# blackfin_c_ethernet.net
KiCad netlist of a schematic drawn in Altium Designer
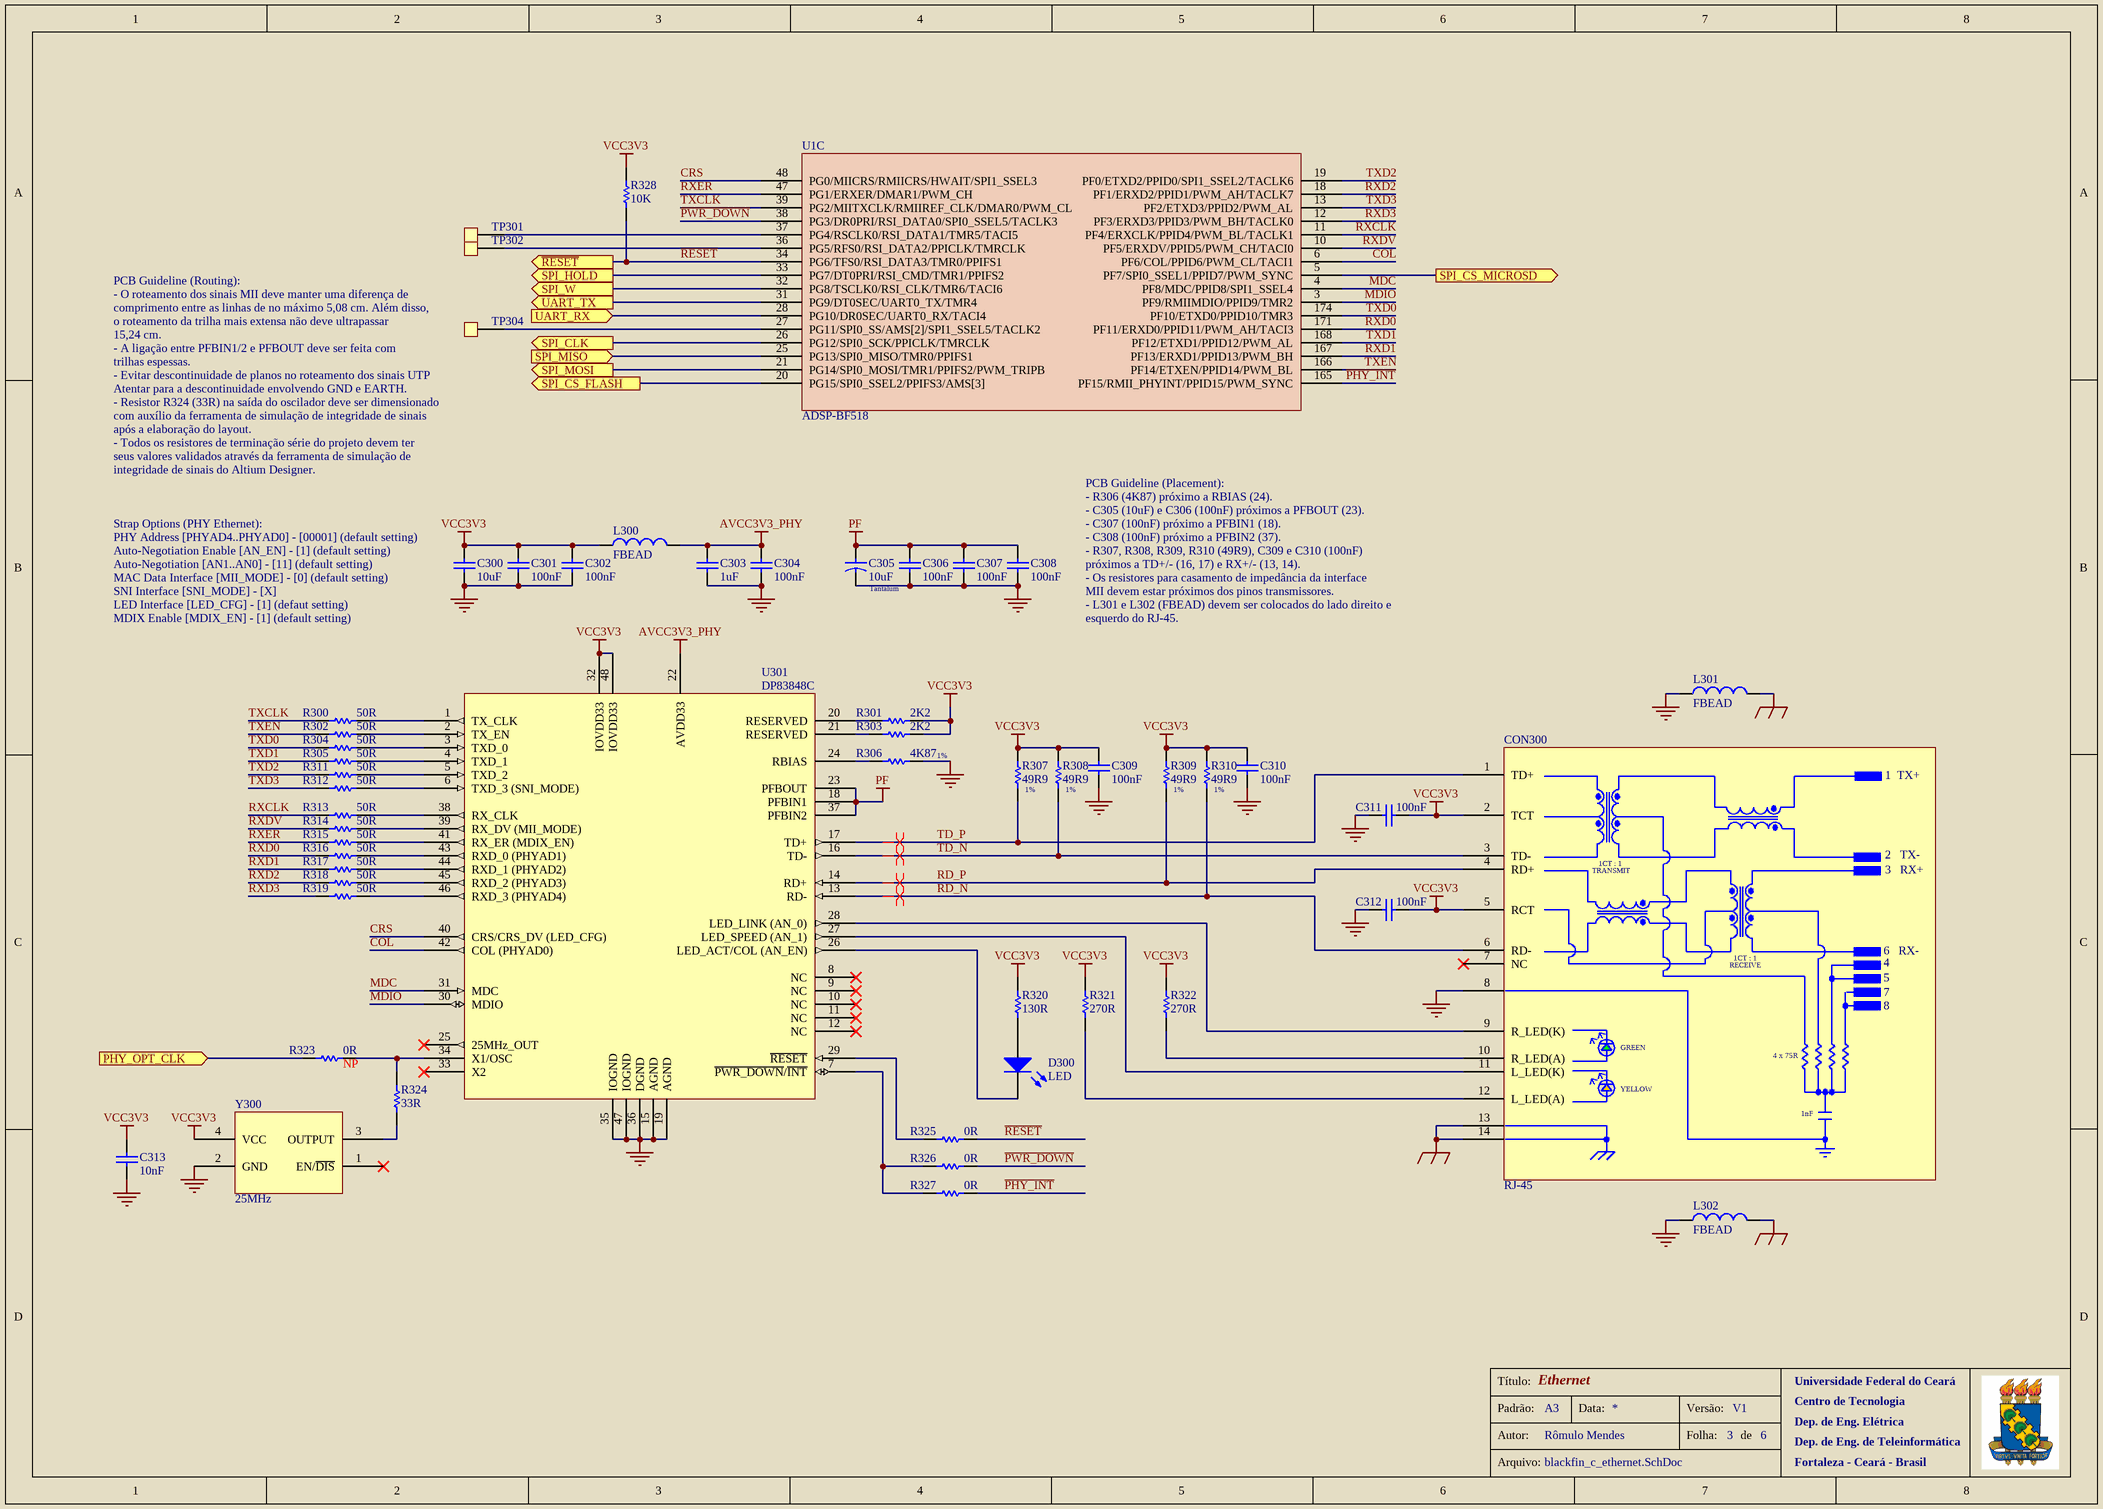
[diagram p0: blackfin_c_ethernet.SchDoc]

(export (version "E")
  (design (tool "Eeschema 10.0.6"))
  (components
    (comp (ref "C300")
      (value "10uF")
      (footprint "blackfin_pcblib:C_0805")
      (fields
        (field (name "EVENDORPART#") "810-C2012Y5V1C106Z")
        (field (name "MANUFACTURER") "TDK")
        (field (name "PART#") "C2012Y5V1C106Z")
      )
      (libsource (lib "blackfin_schlib") (part "Capacitor"))
    )
    (comp (ref "C301")
      (value "100nF")
      (footprint "blackfin_pcblib:C_0603")
      (fields
        (field (name "EVENDORPART#") "81-GRM188R71E104KA01")
        (field (name "MANUFACTURER") "Murata")
        (field (name "PART#") "GRM188R71E104KA01J")
      )
      (libsource (lib "blackfin_schlib") (part "Capacitor"))
    )
    (comp (ref "C302")
      (value "100nF")
      (footprint "blackfin_pcblib:C_0603")
      (fields
        (field (name "EVENDORPART#") "81-GRM188R71E104KA01")
        (field (name "MANUFACTURER") "Murata")
        (field (name "PART#") "GRM188R71E104KA01J")
      )
      (libsource (lib "blackfin_schlib") (part "Capacitor"))
    )
    (comp (ref "C303")
      (value "1uF")
      (footprint "blackfin_pcblib:C_0603")
      (fields
        (field (name "EVENDORPART#") "81-GRM188F51E105ZA12")
        (field (name "MANUFACTURER") "Murata")
        (field (name "PART#") "GRM188F51E105ZA12D")
      )
      (libsource (lib "blackfin_schlib") (part "Capacitor"))
    )
    (comp (ref "C304")
      (value "100nF")
      (footprint "blackfin_pcblib:C_0603")
      (fields
        (field (name "EVENDORPART#") "81-GRM188R71E104KA01")
        (field (name "MANUFACTURER") "Murata")
        (field (name "PART#") "GRM188R71E104KA01J")
      )
      (libsource (lib "blackfin_schlib") (part "Capacitor"))
    )
    (comp (ref "C305")
      (value "10uF")
      (footprint "blackfin_pcblib:C_Case_A")
      (fields
        (field (name "EVENDORPART#") "80-B45196H3106K109")
        (field (name "PART#") "B45196H3106K109V17")
        (field (name "MANUFACTURER") "Kemet")
      )
      (libsource (lib "*") (part "Capacitor_Pol"))
    )
    (comp (ref "C306")
      (value "100nF")
      (footprint "blackfin_pcblib:C_0603")
      (fields
        (field (name "EVENDORPART#") "81-GRM188R71E104KA01")
        (field (name "MANUFACTURER") "Murata")
        (field (name "PART#") "GRM188R71E104KA01J")
      )
      (libsource (lib "blackfin_schlib") (part "Capacitor"))
    )
    (comp (ref "C307")
      (value "100nF")
      (footprint "blackfin_pcblib:C_0603")
      (fields
        (field (name "EVENDORPART#") "81-GRM188R71E104KA01")
        (field (name "MANUFACTURER") "Murata")
        (field (name "PART#") "GRM188R71E104KA01J")
      )
      (libsource (lib "blackfin_schlib") (part "Capacitor"))
    )
    (comp (ref "C308")
      (value "100nF")
      (footprint "blackfin_pcblib:C_0603")
      (fields
        (field (name "EVENDORPART#") "81-GRM188R71E104KA01")
        (field (name "MANUFACTURER") "Murata")
        (field (name "PART#") "GRM188R71E104KA01J")
      )
      (libsource (lib "blackfin_schlib") (part "Capacitor"))
    )
    (comp (ref "C309")
      (value "100nF")
      (footprint "blackfin_pcblib:C_0603")
      (fields
        (field (name "EVENDORPART#") "81-GRM188R71E104KA01")
        (field (name "MANUFACTURER") "Murata")
        (field (name "PART#") "GRM188R71E104KA01J")
      )
      (libsource (lib "blackfin_schlib") (part "Capacitor"))
    )
    (comp (ref "C310")
      (value "100nF")
      (footprint "blackfin_pcblib:C_0603")
      (fields
        (field (name "EVENDORPART#") "81-GRM188R71E104KA01")
        (field (name "MANUFACTURER") "Murata")
        (field (name "PART#") "GRM188R71E104KA01J")
      )
      (libsource (lib "blackfin_schlib") (part "Capacitor"))
    )
    (comp (ref "C311")
      (value "100nF")
      (footprint "blackfin_pcblib:C_0603")
      (fields
        (field (name "EVENDORPART#") "81-GRM188R71E104KA01")
        (field (name "MANUFACTURER") "Murata")
        (field (name "PART#") "GRM188R71E104KA01J")
      )
      (libsource (lib "blackfin_schlib") (part "Capacitor"))
    )
    (comp (ref "C312")
      (value "100nF")
      (footprint "blackfin_pcblib:C_0603")
      (fields
        (field (name "EVENDORPART#") "81-GRM188R71E104KA01")
        (field (name "MANUFACTURER") "Murata")
        (field (name "PART#") "GRM188R71E104KA01J")
      )
      (libsource (lib "blackfin_schlib") (part "Capacitor"))
    )
    (comp (ref "C313")
      (value "10nF")
      (footprint "blackfin_pcblib:C_0603")
      (fields
        (field (name "EVENDORPART#") "77-VJ0603Y103KXAPBC")
        (field (name "MANUFACTURER") "Vishay/Vitramon")
        (field (name "PART#") "VJ0603Y103KXAPW1BC")
      )
      (libsource (lib "blackfin_schlib") (part "Capacitor"))
    )
    (comp (ref "CON300")
      (value "RJ-45")
      (footprint "blackfin_pcblib:RJ-45")
      (fields
        (field (name "EVENDORPART#") "673-J1012F01C")
        (field (name "PART#") "J1012F01C")
        (field (name "MANUFACTURER") "Pulse")
      )
      (libsource (lib "blackfin_schlib") (part "RJ-45"))
    )
    (comp (ref "D300")
      (value "LED")
      (footprint "blackfin_pcblib:LED_0603")
      (description "Green LED")
      (fields (field (name "EVENDORPART#") "638-QTLP600C4") (field (name "MANUFACTURER") "Everlight"))
      (libsource (lib "blackfin_schlib") (part "LED"))
    )
    (comp (ref "L300")
      (value "FBEAD")
      (footprint "blackfin_pcblib:L_0603")
      (fields
        (field (name "EVENDORPART#") "875-MI0603L301R-10")
        (field (name "MANUFACTURER") "Laird Technologies")
        (field (name "PART#") "MI0603L301R-10")
      )
      (libsource (lib "blackfin_schlib") (part "Inductor"))
    )
    (comp (ref "L301")
      (value "FBEAD")
      (footprint "blackfin_pcblib:L_0603")
      (fields
        (field (name "EVENDORPART#") "875-MI0603L301R-10")
        (field (name "MANUFACTURER") "Laird Technologies")
        (field (name "PART#") "MI0603L301R-10")
      )
      (libsource (lib "blackfin_schlib") (part "Inductor"))
    )
    (comp (ref "L302")
      (value "FBEAD")
      (footprint "blackfin_pcblib:L_0603")
      (fields
        (field (name "EVENDORPART#") "875-MI0603L301R-10")
        (field (name "MANUFACTURER") "Laird Technologies")
        (field (name "PART#") "MI0603L301R-10")
      )
      (libsource (lib "blackfin_schlib") (part "Inductor"))
    )
    (comp (ref "R300")
      (value "50R")
      (footprint "blackfin_pcblib:R_0402")
      (fields
        (field (name "EVENDORPART#") "71-CRCW0402-49.9-E3")
        (field (name "PART#") "CRCW040249R9FKED")
        (field (name "MANUFACTURER") "Vishay/Dale")
      )
      (libsource (lib "blackfin_schlib") (part "Resistor"))
    )
    (comp (ref "R301")
      (value "2K2")
      (footprint "blackfin_pcblib:R_0603")
      (fields
        (field (name "EVENDORPART#") "71-CRCW06032K20JNEB")
        (field (name "PART#") "CRCW06032K20JNEB")
        (field (name "MANUFACTURER") "Vishay/Dale")
      )
      (libsource (lib "blackfin_schlib") (part "Resistor"))
    )
    (comp (ref "R302")
      (value "50R")
      (footprint "blackfin_pcblib:R_0402")
      (fields
        (field (name "EVENDORPART#") "71-CRCW0402-49.9-E3")
        (field (name "PART#") "CRCW040249R9FKED")
        (field (name "MANUFACTURER") "Vishay/Dale")
      )
      (libsource (lib "blackfin_schlib") (part "Resistor"))
    )
    (comp (ref "R303")
      (value "2K2")
      (footprint "blackfin_pcblib:R_0603")
      (fields
        (field (name "EVENDORPART#") "71-CRCW06032K20JNEB")
        (field (name "PART#") "CRCW06032K20JNEB")
        (field (name "MANUFACTURER") "Vishay/Dale")
      )
      (libsource (lib "blackfin_schlib") (part "Resistor"))
    )
    (comp (ref "R304")
      (value "50R")
      (footprint "blackfin_pcblib:R_0402")
      (fields
        (field (name "EVENDORPART#") "71-CRCW0402-49.9-E3")
        (field (name "PART#") "CRCW040249R9FKED")
        (field (name "MANUFACTURER") "Vishay/Dale")
      )
      (libsource (lib "blackfin_schlib") (part "Resistor"))
    )
    (comp (ref "R305")
      (value "50R")
      (footprint "blackfin_pcblib:R_0402")
      (fields
        (field (name "EVENDORPART#") "71-CRCW0402-49.9-E3")
        (field (name "PART#") "CRCW040249R9FKED")
        (field (name "MANUFACTURER") "Vishay/Dale")
      )
      (libsource (lib "blackfin_schlib") (part "Resistor"))
    )
    (comp (ref "R306")
      (value "4K87")
      (footprint "blackfin_pcblib:R_0603")
      (fields
        (field (name "EVENDORPART#") "71-CRCW0603-4.87K-E3")
        (field (name "PART#") "CRCW06034K87FKEA")
        (field (name "MANUFACTURER") "Vishay/Dale")
      )
      (libsource (lib "blackfin_schlib") (part "Resistor"))
    )
    (comp (ref "R307")
      (value "49R9")
      (footprint "blackfin_pcblib:R_0603")
      (fields
        (field (name "EVENDORPART#") "71-CRCW060349R9FKEB")
        (field (name "PART#") "CRCW060349R9FKEB")
        (field (name "MANUFACTURER") "Vishay/Dale")
      )
      (libsource (lib "blackfin_schlib") (part "Resistor"))
    )
    (comp (ref "R308")
      (value "49R9")
      (footprint "blackfin_pcblib:R_0603")
      (fields
        (field (name "EVENDORPART#") "71-CRCW060349R9FKEB")
        (field (name "PART#") "CRCW060349R9FKEB")
        (field (name "MANUFACTURER") "Vishay/Dale")
      )
      (libsource (lib "blackfin_schlib") (part "Resistor"))
    )
    (comp (ref "R309")
      (value "49R9")
      (footprint "blackfin_pcblib:R_0603")
      (fields
        (field (name "EVENDORPART#") "71-CRCW060349R9FKEB")
        (field (name "PART#") "CRCW060349R9FKEB")
        (field (name "MANUFACTURER") "Vishay/Dale")
      )
      (libsource (lib "blackfin_schlib") (part "Resistor"))
    )
    (comp (ref "R310")
      (value "49R9")
      (footprint "blackfin_pcblib:R_0603")
      (fields
        (field (name "EVENDORPART#") "71-CRCW060349R9FKEB")
        (field (name "PART#") "CRCW060349R9FKEB")
        (field (name "MANUFACTURER") "Vishay/Dale")
      )
      (libsource (lib "blackfin_schlib") (part "Resistor"))
    )
    (comp (ref "R311")
      (value "50R")
      (footprint "blackfin_pcblib:R_0402")
      (fields
        (field (name "EVENDORPART#") "71-CRCW0402-49.9-E3")
        (field (name "PART#") "CRCW040249R9FKED")
        (field (name "MANUFACTURER") "Vishay/Dale")
      )
      (libsource (lib "blackfin_schlib") (part "Resistor"))
    )
    (comp (ref "R312")
      (value "50R")
      (footprint "blackfin_pcblib:R_0402")
      (fields
        (field (name "EVENDORPART#") "71-CRCW0402-49.9-E3")
        (field (name "PART#") "CRCW040249R9FKED")
        (field (name "MANUFACTURER") "Vishay/Dale")
      )
      (libsource (lib "blackfin_schlib") (part "Resistor"))
    )
    (comp (ref "R313")
      (value "50R")
      (footprint "blackfin_pcblib:R_0402")
      (fields
        (field (name "EVENDORPART#") "71-CRCW0402-49.9-E3")
        (field (name "PART#") "CRCW040249R9FKED")
        (field (name "MANUFACTURER") "Vishay/Dale")
      )
      (libsource (lib "blackfin_schlib") (part "Resistor"))
    )
    (comp (ref "R314")
      (value "50R")
      (footprint "blackfin_pcblib:R_0402")
      (fields
        (field (name "EVENDORPART#") "71-CRCW0402-49.9-E3")
        (field (name "PART#") "CRCW040249R9FKED")
        (field (name "MANUFACTURER") "Vishay/Dale")
      )
      (libsource (lib "blackfin_schlib") (part "Resistor"))
    )
    (comp (ref "R315")
      (value "50R")
      (footprint "blackfin_pcblib:R_0402")
      (fields
        (field (name "EVENDORPART#") "71-CRCW0402-49.9-E3")
        (field (name "PART#") "CRCW040249R9FKED")
        (field (name "MANUFACTURER") "Vishay/Dale")
      )
      (libsource (lib "blackfin_schlib") (part "Resistor"))
    )
    (comp (ref "R316")
      (value "50R")
      (footprint "blackfin_pcblib:R_0402")
      (fields
        (field (name "EVENDORPART#") "71-CRCW0402-49.9-E3")
        (field (name "PART#") "CRCW040249R9FKED")
        (field (name "MANUFACTURER") "Vishay/Dale")
      )
      (libsource (lib "blackfin_schlib") (part "Resistor"))
    )
    (comp (ref "R317")
      (value "50R")
      (footprint "blackfin_pcblib:R_0402")
      (fields
        (field (name "EVENDORPART#") "71-CRCW0402-49.9-E3")
        (field (name "PART#") "CRCW040249R9FKED")
        (field (name "MANUFACTURER") "Vishay/Dale")
      )
      (libsource (lib "blackfin_schlib") (part "Resistor"))
    )
    (comp (ref "R318")
      (value "50R")
      (footprint "blackfin_pcblib:R_0402")
      (fields
        (field (name "EVENDORPART#") "71-CRCW0402-49.9-E3")
        (field (name "PART#") "CRCW040249R9FKED")
        (field (name "MANUFACTURER") "Vishay/Dale")
      )
      (libsource (lib "blackfin_schlib") (part "Resistor"))
    )
    (comp (ref "R319")
      (value "50R")
      (footprint "blackfin_pcblib:R_0402")
      (fields
        (field (name "EVENDORPART#") "71-CRCW0402-49.9-E3")
        (field (name "PART#") "CRCW040249R9FKED")
        (field (name "MANUFACTURER") "Vishay/Dale")
      )
      (libsource (lib "blackfin_schlib") (part "Resistor"))
    )
    (comp (ref "R320")
      (value "130R")
      (footprint "blackfin_pcblib:R_0603")
      (fields
        (field (name "EVENDORPART#") "71-CRCW0603-130-E3")
        (field (name "PART#") "CRCW0603130RFKEA")
        (field (name "MANUFACTURER") "Vishay/Dale")
      )
      (libsource (lib "blackfin_schlib") (part "Resistor"))
    )
    (comp (ref "R321")
      (value "270R")
      (footprint "blackfin_pcblib:R_0603")
      (fields
        (field (name "EVENDORPART#") "71-CRCW0603-270-E3")
        (field (name "PART#") "CRCW0603270RFKEA")
        (field (name "MANUFACTURER") "Vishay/Dale")
      )
      (libsource (lib "blackfin_schlib") (part "Resistor"))
    )
    (comp (ref "R322")
      (value "270R")
      (footprint "blackfin_pcblib:R_0603")
      (fields
        (field (name "EVENDORPART#") "71-CRCW0603-270-E3")
        (field (name "PART#") "CRCW0603270RFKEA")
        (field (name "MANUFACTURER") "Vishay/Dale")
      )
      (libsource (lib "blackfin_schlib") (part "Resistor"))
    )
    (comp (ref "R323")
      (value "0R")
      (footprint "blackfin_pcblib:R_0603")
      (fields
        (field (name "EVENDORPART#") "71-CRCW06030000Z0EB")
        (field (name "PART#") "CRCW06030000Z0EB")
        (field (name "MANUFACTURER") "Vishay/Dale")
      )
      (libsource (lib "blackfin_schlib") (part "Resistor"))
    )
    (comp (ref "R324")
      (value "33R")
      (footprint "blackfin_pcblib:R_0402")
      (fields
        (field (name "EVENDORPART#") "71-CRCW0402J-33-E3")
        (field (name "PART#") "CRCW040233R0JNED")
        (field (name "MANUFACTURER") "Vishay/Dale")
      )
      (libsource (lib "blackfin_schlib") (part "Resistor"))
    )
    (comp (ref "R325")
      (value "0R")
      (footprint "blackfin_pcblib:R_0603")
      (fields
        (field (name "EVENDORPART#") "71-CRCW06030000Z0EB")
        (field (name "PART#") "CRCW06030000Z0EB")
        (field (name "MANUFACTURER") "Vishay/Dale")
      )
      (libsource (lib "blackfin_schlib") (part "Resistor"))
    )
    (comp (ref "R326")
      (value "0R")
      (footprint "blackfin_pcblib:R_0603")
      (fields
        (field (name "EVENDORPART#") "71-CRCW06030000Z0EB")
        (field (name "PART#") "CRCW06030000Z0EB")
        (field (name "MANUFACTURER") "Vishay/Dale")
      )
      (libsource (lib "blackfin_schlib") (part "Resistor"))
    )
    (comp (ref "R327")
      (value "0R")
      (footprint "blackfin_pcblib:R_0603")
      (fields
        (field (name "EVENDORPART#") "71-CRCW06030000Z0EB")
        (field (name "PART#") "CRCW06030000Z0EB")
        (field (name "MANUFACTURER") "Vishay/Dale")
      )
      (libsource (lib "blackfin_schlib") (part "Resistor"))
    )
    (comp (ref "R328")
      (value "10K")
      (footprint "blackfin_pcblib:R_0603")
      (fields
        (field (name "EVENDORPART#") "71-CRCW0603-10K-E3")
        (field (name "PART#") "CRCW060310K0FKEA")
        (field (name "MANUFACTURER") "Vishay/Dale")
      )
      (libsource (lib "blackfin_schlib") (part "Resistor"))
    )
    (comp (ref "TP301")
      (value "Test Point")
      (footprint "blackfin_pcblib:Test Point")
      (fields (field (name "EVENDORPART#") "NÃO SE APLICA"))
      (libsource (lib "blackfin_schlib") (part "Test Point"))
    )
    (comp (ref "TP302")
      (value "Test Point")
      (footprint "blackfin_pcblib:Test Point")
      (fields (field (name "EVENDORPART#") "NÃO SE APLICA"))
      (libsource (lib "blackfin_schlib") (part "Test Point"))
    )
    (comp (ref "TP304")
      (value "Test Point")
      (footprint "blackfin_pcblib:Test Point")
      (fields (field (name "EVENDORPART#") "NÃO SE APLICA"))
      (libsource (lib "blackfin_schlib") (part "Test Point"))
    )
    (comp (ref "U1")
      (value "ADSP-BF518")
      (footprint "blackfin_pcblib:LQFP-176")
      (fields (field (name "EVENDORPART#") "ADSP-BF518BSWZ-4") (field (name "MANUFACTURER") "Analog Devices"))
      (libsource (lib "blackfin_schlib") (part "ADSP-BF518"))
    )
    (comp (ref "U301")
      (value "DP83848C")
      (footprint "blackfin_pcblib:LQFP-48")
      (fields
        (field (name "MANUFACTURER") "National Semiconductor")
        (field (name "PART#") "DP83848CVV/NOPB")
        (field (name "EVENDORPART#") "DP83848CVV-ND")
      )
      (libsource (lib "blackfin_schlib") (part "DP83848C"))
    )
    (comp (ref "Y300")
      (value "25MHz")
      (footprint "blackfin_pcblib:OSC_25MHz")
      (fields
        (field (name "EVENDORPART#") "815-ASV-25-EJ-T")
        (field (name "PART#") "ASV-25.000MHZ-EJ-T")
        (field (name "MANUFACTURER") "ABRACON")
      )
      (libsource (lib "blackfin_schlib") (part "Oscillator_25MHz"))
    )
  )
  (nets
    (net (code "1") (name "/COL") (class "Default")
      (node (ref "U1") (pin "6") (pinfunction "PF6/COL/PPID6/PWM_CL/TACI1_6") (pintype "passive"))
      (node (ref "U301") (pin "42") (pinfunction "COL_(PHYAD0)_42") (pintype "output"))
    )
    (net (code "2") (name "/CRS") (class "Default")
      (node (ref "U1") (pin "48") (pinfunction "PG0/MIICRS/RMIICRS/HWAIT/SPI1_SSEL3_48") (pintype "passive"))
      (node (ref "U301") (pin "40") (pinfunction "CRS/CRS_DV_(LED_CFG)_40") (pintype "output"))
    )
    (net (code "3") (name "/MDC") (class "Default")
      (node (ref "U1") (pin "4") (pinfunction "PF8/MDC/PPID8/SPI1_SSEL4_4") (pintype "passive"))
      (node (ref "U301") (pin "31") (pinfunction "MDC_31") (pintype "input"))
    )
    (net (code "4") (name "/MDIO") (class "Default")
      (node (ref "U1") (pin "3") (pinfunction "PF9/RMIIMDIO/PPID9/TMR2_3") (pintype "passive"))
      (node (ref "U301") (pin "30") (pinfunction "MDIO_30") (pintype "bidirectional"))
    )
    (net (code "5") (name "/PHY_OPT_CLK") (class "Default")
      (node (ref "R323") (pin "1") (pinfunction "1_1") (pintype "passive"))
    )
    (net (code "6") (name "/RD_N") (class "Default")
      (node (ref "CON300") (pin "6") (pinfunction "RD-_6") (pintype "passive"))
      (node (ref "R310") (pin "1") (pinfunction "1_1") (pintype "passive"))
      (node (ref "U301") (pin "13") (pinfunction "RD-_13") (pintype "input"))
    )
    (net (code "7") (name "/RD_P") (class "Default")
      (node (ref "CON300") (pin "4") (pinfunction "RD+_4") (pintype "passive"))
      (node (ref "R309") (pin "1") (pinfunction "1_1") (pintype "passive"))
      (node (ref "U301") (pin "14") (pinfunction "RD+_14") (pintype "input"))
    )
    (net (code "8") (name "/RXCLK") (class "Default")
      (node (ref "R313") (pin "1") (pinfunction "1_1") (pintype "passive"))
      (node (ref "U1") (pin "11") (pinfunction "PF4/ERXCLK/PPID4/PWM_BL/TACLK1_11") (pintype "passive"))
    )
    (net (code "9") (name "/RXD0") (class "Default")
      (node (ref "R316") (pin "1") (pinfunction "1_1") (pintype "passive"))
      (node (ref "U1") (pin "171") (pinfunction "PF11/ERXD0/PPID11/PWM_AH/TACI3_171") (pintype "passive"))
    )
    (net (code "10") (name "/RXD1") (class "Default")
      (node (ref "R317") (pin "1") (pinfunction "1_1") (pintype "passive"))
      (node (ref "U1") (pin "167") (pinfunction "PF13/ERXD1/PPID13/PWM_BH_167") (pintype "passive"))
    )
    (net (code "11") (name "/RXD2") (class "Default")
      (node (ref "R318") (pin "1") (pinfunction "1_1") (pintype "passive"))
      (node (ref "U1") (pin "18") (pinfunction "PF1/ERXD2/PPID1/PWM_AH/TACLK7_18") (pintype "passive"))
    )
    (net (code "12") (name "/RXD3") (class "Default")
      (node (ref "R319") (pin "1") (pinfunction "1_1") (pintype "passive"))
      (node (ref "U1") (pin "12") (pinfunction "PF3/ERXD3/PPID3/PWM_BH/TACLK0_12") (pintype "passive"))
    )
    (net (code "13") (name "/RXDV") (class "Default")
      (node (ref "R314") (pin "1") (pinfunction "1_1") (pintype "passive"))
      (node (ref "U1") (pin "10") (pinfunction "PF5/ERXDV/PPID5/PWM_CH/TACI0_10") (pintype "passive"))
    )
    (net (code "14") (name "/RXER") (class "Default")
      (node (ref "R315") (pin "1") (pinfunction "1_1") (pintype "passive"))
      (node (ref "U1") (pin "47") (pinfunction "PG1/ERXER/DMAR1/PWM_CH_47") (pintype "passive"))
    )
    (net (code "15") (name "/SPI_CLK") (class "Default")
      (node (ref "U1") (pin "26") (pinfunction "PG12/SPI0_SCK/PPICLK/TMRCLK_26") (pintype "passive"))
    )
    (net (code "16") (name "/SPI_CS_FLASH") (class "Default")
      (node (ref "U1") (pin "20") (pinfunction "PG15/SPI0_SSEL2/PPIFS3/AMS[3]_20") (pintype "passive"))
    )
    (net (code "17") (name "/SPI_CS_MICROSD") (class "Default")
      (node (ref "U1") (pin "5") (pinfunction "PF7/SPI0_SSEL1/PPID7/PWM_SYNC_5") (pintype "passive"))
    )
    (net (code "18") (name "/SPI_HOLD") (class "Default")
      (node (ref "U1") (pin "33") (pinfunction "PG7/DT0PRI/RSI_CMD/TMR1/PPIFS2_33") (pintype "passive"))
    )
    (net (code "19") (name "/SPI_MISO") (class "Default")
      (node (ref "U1") (pin "25") (pinfunction "PG13/SPI0_MISO/TMR0/PPIFS1_25") (pintype "passive"))
    )
    (net (code "20") (name "/SPI_MOSI") (class "Default")
      (node (ref "U1") (pin "21") (pinfunction "PG14/SPI0_MOSI/TMR1/PPIFS2/PWM_TRIPB_21") (pintype "passive"))
    )
    (net (code "21") (name "/SPI_W") (class "Default")
      (node (ref "U1") (pin "32") (pinfunction "PG8/TSCLK0/RSI_CLK/TMR6/TACI6_32") (pintype "passive"))
    )
    (net (code "22") (name "/TD_N") (class "Default")
      (node (ref "CON300") (pin "3") (pinfunction "TD-_3") (pintype "passive"))
      (node (ref "R308") (pin "1") (pinfunction "1_1") (pintype "passive"))
      (node (ref "U301") (pin "16") (pinfunction "TD-_16") (pintype "output"))
    )
    (net (code "23") (name "/TD_P") (class "Default")
      (node (ref "CON300") (pin "1") (pinfunction "TD+_1") (pintype "passive"))
      (node (ref "R307") (pin "1") (pinfunction "1_1") (pintype "passive"))
      (node (ref "U301") (pin "17") (pinfunction "TD+_17") (pintype "output"))
    )
    (net (code "24") (name "/TXCLK") (class "Default")
      (node (ref "R300") (pin "1") (pinfunction "1_1") (pintype "passive"))
      (node (ref "U1") (pin "39") (pinfunction "PG2/MIITXCLK/RMIIREF_CLK/DMAR0/PWM_CL_39") (pintype "passive"))
    )
    (net (code "25") (name "/TXD0") (class "Default")
      (node (ref "R304") (pin "1") (pinfunction "1_1") (pintype "passive"))
      (node (ref "U1") (pin "174") (pinfunction "PF10/ETXD0/PPID10/TMR3_174") (pintype "passive"))
    )
    (net (code "26") (name "/TXD1") (class "Default")
      (node (ref "R305") (pin "1") (pinfunction "1_1") (pintype "passive"))
      (node (ref "U1") (pin "168") (pinfunction "PF12/ETXD1/PPID12/PWM_AL_168") (pintype "passive"))
    )
    (net (code "27") (name "/TXD2") (class "Default")
      (node (ref "R311") (pin "1") (pinfunction "1_1") (pintype "passive"))
      (node (ref "U1") (pin "19") (pinfunction "PF0/ETXD2/PPID0/SPI1_SSEL2/TACLK6_19") (pintype "passive"))
    )
    (net (code "28") (name "/TXD3") (class "Default")
      (node (ref "R312") (pin "1") (pinfunction "1_1") (pintype "passive"))
      (node (ref "U1") (pin "13") (pinfunction "PF2/ETXD3/PPID2/PWM_AL_13") (pintype "passive"))
    )
    (net (code "29") (name "/TXEN") (class "Default")
      (node (ref "R302") (pin "1") (pinfunction "1_1") (pintype "passive"))
      (node (ref "U1") (pin "166") (pinfunction "PF14/ETXEN/PPID14/PWM_BL_166") (pintype "passive"))
    )
    (net (code "30") (name "/UART_RX") (class "Default")
      (node (ref "U1") (pin "28") (pinfunction "PG10/DR0SEC/UART0_RX/TACI4_28") (pintype "passive"))
    )
    (net (code "31") (name "/UART_TX") (class "Default")
      (node (ref "U1") (pin "31") (pinfunction "PG9/DT0SEC/UART0_TX/TMR4_31") (pintype "passive"))
    )
    (net (code "32") (name "/~{PHY_INT}") (class "Default")
      (node (ref "R327") (pin "2") (pinfunction "2_2") (pintype "passive"))
      (node (ref "U1") (pin "165") (pinfunction "PF15/RMII_PHYINT/PPID15/PWM_SYNC_165") (pintype "passive"))
    )
    (net (code "33") (name "/~{PWR_DOWN}") (class "Default")
      (node (ref "R326") (pin "2") (pinfunction "2_2") (pintype "passive"))
      (node (ref "U1") (pin "38") (pinfunction "PG3/DR0PRI/RSI_DATA0/SPI0_SSEL5/TACLK3_38") (pintype "passive"))
    )
    (net (code "34") (name "/~{RESET}") (class "Default")
      (node (ref "R325") (pin "2") (pinfunction "2_2") (pintype "passive"))
      (node (ref "R328") (pin "2") (pinfunction "2_2") (pintype "passive"))
      (node (ref "U1") (pin "34") (pinfunction "PG6/TFS0/RSI_DATA3/TMR0/PPIFS1_34") (pintype "passive"))
    )
    (net (code "35") (name "AVCC3V3_PHY") (class "Default")
      (node (ref "C303") (pin "2") (pinfunction "2_2") (pintype "passive"))
      (node (ref "C304") (pin "2") (pinfunction "2_2") (pintype "passive"))
      (node (ref "L300") (pin "2") (pinfunction "2_2") (pintype "passive"))
      (node (ref "U301") (pin "22") (pinfunction "AVDD33_22") (pintype "power_in"))
    )
    (net (code "36") (name "EARTH_ETH") (class "Default")
      (node (ref "CON300") (pin "13") (pinfunction "GND_13") (pintype "passive"))
      (node (ref "CON300") (pin "14") (pinfunction "GND_14") (pintype "passive"))
      (node (ref "L301") (pin "2") (pinfunction "2_2") (pintype "passive"))
      (node (ref "L302") (pin "2") (pinfunction "2_2") (pintype "passive"))
    )
    (net (code "37") (name "GND") (class "Default")
      (node (ref "C300") (pin "1") (pinfunction "1_1") (pintype "passive"))
      (node (ref "C301") (pin "1") (pinfunction "1_1") (pintype "passive"))
      (node (ref "C302") (pin "1") (pinfunction "1_1") (pintype "passive"))
      (node (ref "C303") (pin "1") (pinfunction "1_1") (pintype "passive"))
      (node (ref "C304") (pin "1") (pinfunction "1_1") (pintype "passive"))
      (node (ref "C305") (pin "2") (pinfunction "2_2") (pintype "passive"))
      (node (ref "C306") (pin "1") (pinfunction "1_1") (pintype "passive"))
      (node (ref "C307") (pin "1") (pinfunction "1_1") (pintype "passive"))
      (node (ref "C308") (pin "1") (pinfunction "1_1") (pintype "passive"))
      (node (ref "C309") (pin "1") (pinfunction "1_1") (pintype "passive"))
      (node (ref "C310") (pin "1") (pinfunction "1_1") (pintype "passive"))
      (node (ref "C311") (pin "2") (pinfunction "2_2") (pintype "passive"))
      (node (ref "C312") (pin "2") (pinfunction "2_2") (pintype "passive"))
      (node (ref "C313") (pin "1") (pinfunction "1_1") (pintype "passive"))
      (node (ref "CON300") (pin "8") (pinfunction "GND_8") (pintype "passive"))
      (node (ref "L301") (pin "1") (pinfunction "1_1") (pintype "passive"))
      (node (ref "L302") (pin "1") (pinfunction "1_1") (pintype "passive"))
      (node (ref "R306") (pin "1") (pinfunction "1_1") (pintype "passive"))
      (node (ref "U301") (pin "15") (pinfunction "AGND_15") (pintype "power_in"))
      (node (ref "U301") (pin "19") (pinfunction "AGND_19") (pintype "power_in"))
      (node (ref "U301") (pin "35") (pinfunction "IOGND_35") (pintype "power_in"))
      (node (ref "U301") (pin "36") (pinfunction "DGND_36") (pintype "power_in"))
      (node (ref "U301") (pin "47") (pinfunction "IOGND_47") (pintype "power_in"))
      (node (ref "Y300") (pin "2") (pinfunction "GND_2") (pintype "passive"))
    )
    (net (code "38") (name "Net-(CON300-L_LED(A))") (class "Default")
      (node (ref "CON300") (pin "12") (pinfunction "L_LED(A)_12") (pintype "passive"))
      (node (ref "R321") (pin "1") (pinfunction "1_1") (pintype "passive"))
    )
    (net (code "39") (name "Net-(CON300-L_LED(K))") (class "Default")
      (node (ref "CON300") (pin "11") (pinfunction "L_LED(K)_11") (pintype "passive"))
      (node (ref "U301") (pin "27") (pinfunction "LED_SPEED_(AN_1)_27") (pintype "output"))
    )
    (net (code "40") (name "Net-(CON300-R_LED(A))") (class "Default")
      (node (ref "CON300") (pin "10") (pinfunction "R_LED(A)_10") (pintype "passive"))
      (node (ref "R322") (pin "1") (pinfunction "1_1") (pintype "passive"))
    )
    (net (code "41") (name "Net-(CON300-R_LED(K))") (class "Default")
      (node (ref "CON300") (pin "9") (pinfunction "R_LED(K)_9") (pintype "passive"))
      (node (ref "U301") (pin "28") (pinfunction "LED_LINK_(AN_0)_28") (pintype "output"))
    )
    (net (code "42") (name "Net-(D300-A)") (class "Default")
      (node (ref "D300") (pin "1") (pinfunction "A_1") (pintype "passive"))
      (node (ref "R320") (pin "1") (pinfunction "1_1") (pintype "passive"))
    )
    (net (code "43") (name "Net-(D300-K)") (class "Default")
      (node (ref "D300") (pin "2") (pinfunction "K_2") (pintype "passive"))
      (node (ref "U301") (pin "26") (pinfunction "LED_ACT/COL_(AN_EN)_26") (pintype "output"))
    )
    (net (code "44") (name "Net-(R301-Pad2)") (class "Default")
      (node (ref "R301") (pin "2") (pinfunction "2_2") (pintype "passive"))
      (node (ref "U301") (pin "20") (pinfunction "RESERVED_20") (pintype "passive"))
    )
    (net (code "45") (name "Net-(R303-Pad2)") (class "Default")
      (node (ref "R303") (pin "2") (pinfunction "2_2") (pintype "passive"))
      (node (ref "U301") (pin "21") (pinfunction "RESERVED_21") (pintype "passive"))
    )
    (net (code "46") (name "Net-(U1C-PG4{slash}RSCLK0{slash}RSI_DATA1{slash}TMR5{slash}TACI5)") (class "Default")
      (node (ref "TP301") (pin "1") (pinfunction "1_1") (pintype "passive"))
      (node (ref "U1") (pin "37") (pinfunction "PG4/RSCLK0/RSI_DATA1/TMR5/TACI5_37") (pintype "passive"))
    )
    (net (code "47") (name "Net-(U1C-PG5{slash}RFS0{slash}RSI_DATA2{slash}PPICLK{slash}TMRCLK)") (class "Default")
      (node (ref "TP302") (pin "1") (pinfunction "1_1") (pintype "passive"))
      (node (ref "U1") (pin "36") (pinfunction "PG5/RFS0/RSI_DATA2/PPICLK/TMRCLK_36") (pintype "passive"))
    )
    (net (code "48") (name "Net-(U1C-PG11{slash}SPI0_SS{slash}AMS[2]{slash}SPI1_SSEL5{slash}TACLK2)") (class "Default")
      (node (ref "TP304") (pin "1") (pinfunction "1_1") (pintype "passive"))
      (node (ref "U1") (pin "27") (pinfunction "PG11/SPI0_SS/AMS[2]/SPI1_SSEL5/TACLK2_27") (pintype "passive"))
    )
    (net (code "49") (name "Net-(U301-RBIAS)") (class "Default")
      (node (ref "R306") (pin "2") (pinfunction "2_2") (pintype "passive"))
      (node (ref "U301") (pin "24") (pinfunction "RBIAS_24") (pintype "passive"))
    )
    (net (code "50") (name "Net-(U301-RXD_0_(PHYAD1))") (class "Default")
      (node (ref "R316") (pin "2") (pinfunction "2_2") (pintype "passive"))
      (node (ref "U301") (pin "43") (pinfunction "RXD_0_(PHYAD1)_43") (pintype "output"))
    )
    (net (code "51") (name "Net-(U301-RXD_1_(PHYAD2))") (class "Default")
      (node (ref "R317") (pin "2") (pinfunction "2_2") (pintype "passive"))
      (node (ref "U301") (pin "44") (pinfunction "RXD_1_(PHYAD2)_44") (pintype "output"))
    )
    (net (code "52") (name "Net-(U301-RXD_2_(PHYAD3))") (class "Default")
      (node (ref "R318") (pin "2") (pinfunction "2_2") (pintype "passive"))
      (node (ref "U301") (pin "45") (pinfunction "RXD_2_(PHYAD3)_45") (pintype "output"))
    )
    (net (code "53") (name "Net-(U301-RXD_3_(PHYAD4))") (class "Default")
      (node (ref "R319") (pin "2") (pinfunction "2_2") (pintype "passive"))
      (node (ref "U301") (pin "46") (pinfunction "RXD_3_(PHYAD4)_46") (pintype "output"))
    )
    (net (code "54") (name "Net-(U301-RX_CLK)") (class "Default")
      (node (ref "R313") (pin "2") (pinfunction "2_2") (pintype "passive"))
      (node (ref "U301") (pin "38") (pinfunction "RX_CLK_38") (pintype "output"))
    )
    (net (code "55") (name "Net-(U301-RX_DV_(MII_MODE))") (class "Default")
      (node (ref "R314") (pin "2") (pinfunction "2_2") (pintype "passive"))
      (node (ref "U301") (pin "39") (pinfunction "RX_DV_(MII_MODE)_39") (pintype "output"))
    )
    (net (code "56") (name "Net-(U301-RX_ER_(MDIX_EN))") (class "Default")
      (node (ref "R315") (pin "2") (pinfunction "2_2") (pintype "passive"))
      (node (ref "U301") (pin "41") (pinfunction "RX_ER_(MDIX_EN)_41") (pintype "output"))
    )
    (net (code "57") (name "Net-(U301-TXD_0)") (class "Default")
      (node (ref "R304") (pin "2") (pinfunction "2_2") (pintype "passive"))
      (node (ref "U301") (pin "3") (pinfunction "TXD_0_3") (pintype "input"))
    )
    (net (code "58") (name "Net-(U301-TXD_1)") (class "Default")
      (node (ref "R305") (pin "2") (pinfunction "2_2") (pintype "passive"))
      (node (ref "U301") (pin "4") (pinfunction "TXD_1_4") (pintype "input"))
    )
    (net (code "59") (name "Net-(U301-TXD_2)") (class "Default")
      (node (ref "R311") (pin "2") (pinfunction "2_2") (pintype "passive"))
      (node (ref "U301") (pin "5") (pinfunction "TXD_2_5") (pintype "input"))
    )
    (net (code "60") (name "Net-(U301-TXD_3_(SNI_MODE))") (class "Default")
      (node (ref "R312") (pin "2") (pinfunction "2_2") (pintype "passive"))
      (node (ref "U301") (pin "6") (pinfunction "TXD_3_(SNI_MODE)_6") (pintype "input"))
    )
    (net (code "61") (name "Net-(U301-TX_CLK)") (class "Default")
      (node (ref "R300") (pin "2") (pinfunction "2_2") (pintype "passive"))
      (node (ref "U301") (pin "1") (pinfunction "TX_CLK_1") (pintype "output"))
    )
    (net (code "62") (name "Net-(U301-TX_EN)") (class "Default")
      (node (ref "R302") (pin "2") (pinfunction "2_2") (pintype "passive"))
      (node (ref "U301") (pin "2") (pinfunction "TX_EN_2") (pintype "input"))
    )
    (net (code "63") (name "Net-(U301-X1{slash}OSC)") (class "Default")
      (node (ref "R323") (pin "2") (pinfunction "2_2") (pintype "passive"))
      (node (ref "R324") (pin "2") (pinfunction "2_2") (pintype "passive"))
      (node (ref "U301") (pin "34") (pinfunction "X1/OSC_34") (pintype "passive"))
    )
    (net (code "64") (name "Net-(U301-~{PWR_DOWN}{slash}~{INT})") (class "Default")
      (node (ref "R326") (pin "1") (pinfunction "1_1") (pintype "passive"))
      (node (ref "R327") (pin "1") (pinfunction "1_1") (pintype "passive"))
      (node (ref "U301") (pin "7") (pinfunction "~{PWR_DOWN}/~{INT}_7") (pintype "bidirectional"))
    )
    (net (code "65") (name "Net-(U301-~{RESET})") (class "Default")
      (node (ref "R325") (pin "1") (pinfunction "1_1") (pintype "passive"))
      (node (ref "U301") (pin "29") (pinfunction "~{RESET}_29") (pintype "input"))
    )
    (net (code "66") (name "Net-(Y300-OUTPUT)") (class "Default")
      (node (ref "R324") (pin "1") (pinfunction "1_1") (pintype "passive"))
      (node (ref "Y300") (pin "3") (pinfunction "OUTPUT_3") (pintype "passive"))
    )
    (net (code "67") (name "PF") (class "Default")
      (node (ref "C305") (pin "1") (pinfunction "1_1") (pintype "passive"))
      (node (ref "C306") (pin "2") (pinfunction "2_2") (pintype "passive"))
      (node (ref "C307") (pin "2") (pinfunction "2_2") (pintype "passive"))
      (node (ref "C308") (pin "2") (pinfunction "2_2") (pintype "passive"))
      (node (ref "U301") (pin "18") (pinfunction "PFBIN1_18") (pintype "passive"))
      (node (ref "U301") (pin "23") (pinfunction "PFBOUT_23") (pintype "passive"))
      (node (ref "U301") (pin "37") (pinfunction "PFBIN2_37") (pintype "passive"))
    )
    (net (code "68") (name "VCC3V3") (class "Default")
      (node (ref "C300") (pin "2") (pinfunction "2_2") (pintype "passive"))
      (node (ref "C301") (pin "2") (pinfunction "2_2") (pintype "passive"))
      (node (ref "C302") (pin "2") (pinfunction "2_2") (pintype "passive"))
      (node (ref "C309") (pin "2") (pinfunction "2_2") (pintype "passive"))
      (node (ref "C310") (pin "2") (pinfunction "2_2") (pintype "passive"))
      (node (ref "C311") (pin "1") (pinfunction "1_1") (pintype "passive"))
      (node (ref "C312") (pin "1") (pinfunction "1_1") (pintype "passive"))
      (node (ref "C313") (pin "2") (pinfunction "2_2") (pintype "passive"))
      (node (ref "CON300") (pin "2") (pinfunction "TCT_2") (pintype "passive"))
      (node (ref "CON300") (pin "5") (pinfunction "RCT_5") (pintype "passive"))
      (node (ref "L300") (pin "1") (pinfunction "1_1") (pintype "passive"))
      (node (ref "R301") (pin "1") (pinfunction "1_1") (pintype "passive"))
      (node (ref "R303") (pin "1") (pinfunction "1_1") (pintype "passive"))
      (node (ref "R307") (pin "2") (pinfunction "2_2") (pintype "passive"))
      (node (ref "R308") (pin "2") (pinfunction "2_2") (pintype "passive"))
      (node (ref "R309") (pin "2") (pinfunction "2_2") (pintype "passive"))
      (node (ref "R310") (pin "2") (pinfunction "2_2") (pintype "passive"))
      (node (ref "R320") (pin "2") (pinfunction "2_2") (pintype "passive"))
      (node (ref "R321") (pin "2") (pinfunction "2_2") (pintype "passive"))
      (node (ref "R322") (pin "2") (pinfunction "2_2") (pintype "passive"))
      (node (ref "R328") (pin "1") (pinfunction "1_1") (pintype "passive"))
      (node (ref "U301") (pin "32") (pinfunction "IOVDD33_32") (pintype "power_in"))
      (node (ref "U301") (pin "48") (pinfunction "IOVDD33_48") (pintype "power_in"))
      (node (ref "Y300") (pin "4") (pinfunction "VCC_4") (pintype "passive"))
    )
    (net (code "69") (name "unconnected-(CON300-NC-Pad7)") (class "Default")
      (node (ref "CON300") (pin "7") (pinfunction "NC_7") (pintype "passive+no_connect"))
    )
    (net (code "70") (name "unconnected-(U301-25MHz_OUT-Pad25)") (class "Default")
      (node (ref "U301") (pin "25") (pinfunction "25MHz_OUT_25") (pintype "output+no_connect"))
    )
    (net (code "71") (name "unconnected-(U301-NC-Pad8)") (class "Default")
      (node (ref "U301") (pin "8") (pinfunction "NC_8") (pintype "passive+no_connect"))
    )
    (net (code "72") (name "unconnected-(U301-NC-Pad9)") (class "Default")
      (node (ref "U301") (pin "9") (pinfunction "NC_9") (pintype "passive+no_connect"))
    )
    (net (code "73") (name "unconnected-(U301-NC-Pad10)") (class "Default")
      (node (ref "U301") (pin "10") (pinfunction "NC_10") (pintype "passive+no_connect"))
    )
    (net (code "74") (name "unconnected-(U301-NC-Pad11)") (class "Default")
      (node (ref "U301") (pin "11") (pinfunction "NC_11") (pintype "passive+no_connect"))
    )
    (net (code "75") (name "unconnected-(U301-NC-Pad12)") (class "Default")
      (node (ref "U301") (pin "12") (pinfunction "NC_12") (pintype "passive+no_connect"))
    )
    (net (code "76") (name "unconnected-(U301-X2-Pad33)") (class "Default")
      (node (ref "U301") (pin "33") (pinfunction "X2_33") (pintype "passive+no_connect"))
    )
    (net (code "77") (name "unconnected-(Y300-EN{slash}~{DIS}-Pad1)") (class "Default")
      (node (ref "Y300") (pin "1") (pinfunction "EN/~{DIS}_1") (pintype "passive+no_connect"))
    )
  )
)
